# MCU.net
KiCad netlist of a schematic drawn in Altium Designer
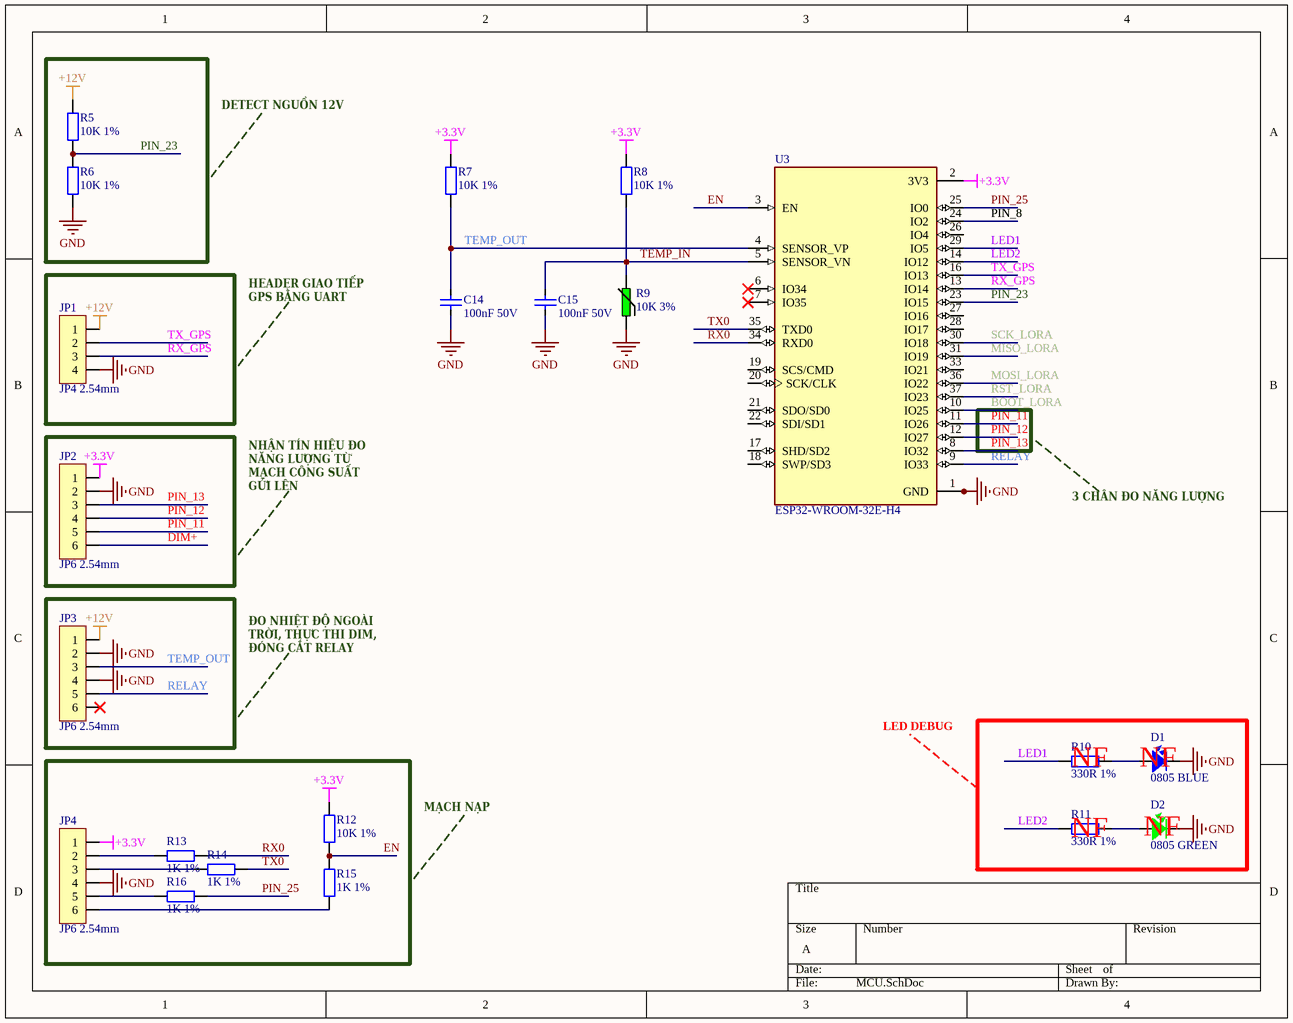
[diagram p0: MCU.SchDoc]

(export (version "E")
  (design (tool "Eeschema 10.0.6"))
  (components
    (comp (ref "C14")
      (value "100nF 50V")
      (footprint "CAP_SMD_0805")
      (description "0.1 µF ±10% 50V Ceramic Capacitor X7R 0805 (2012 Metric)")
      (fields
        (field (name "MANUFACTURER") "YAGEO")
        (field (name "MANUFACTURE PART NUMBER") "CC0805KRX7R9BB104")
      )
      (libsource (lib "Nhatkhongbuon") (part "C0805_MLCC_100nF_50V"))
    )
    (comp (ref "C15")
      (value "100nF 50V")
      (footprint "CAP_SMD_0805")
      (description "0.1 µF ±10% 50V Ceramic Capacitor X7R 0805 (2012 Metric)")
      (fields
        (field (name "MANUFACTURER") "YAGEO")
        (field (name "MANUFACTURE PART NUMBER") "CC0805KRX7R9BB104")
      )
      (libsource (lib "Nhatkhongbuon") (part "C0805_MLCC_100nF_50V"))
    )
    (comp (ref "D1")
      (value "0805 BLUE")
      (footprint "LED-0805-Blue")
      (description "Blue 470nm LED Indication - Discrete 3.2V 0805 (2012 Metric)")
      (fields
        (field (name "MANUFACTURER") "Würth Elektronik")
        (field (name "MANUFACTURE PART NUMBER") "150080BS75000")
      )
      (libsource (lib "Nhatkhongbuon") (part "LED_0805_BLUE"))
    )
    (comp (ref "D2")
      (value "0805 GREEN")
      (footprint "LED-0805-Green")
      (description "Green 520nm LED Indication - Discrete 3.2V 0805 (2012 Metric)")
      (fields
        (field (name "MANUFACTURER") "Würth Elektronik")
        (field (name "MANUFACTURE PART NUMBER") "150080GS75000")
      )
      (libsource (lib "Nhatkhongbuon") (part "LED_0805_GREEN"))
    )
    (comp (ref "JP1")
      (value "JP4 2.54mm")
      (footprint "JP4_M")
      (description "Connector Header Through Hole 4 position 0.100\" (2.54mm)")
      (fields
        (field (name "MANUFACTURER") "Würth Elektronik")
        (field (name "MANUFACTURE PART NUMBER") "61300411121")
      )
      (libsource (lib "Nhatkhongbuon") (part "JP4M"))
    )
    (comp (ref "JP2")
      (value "JP6 2.54mm")
      (footprint "JP6_M")
      (description "Connector Header Through Hole 6 position 0.100\" (2.54mm)")
      (fields
        (field (name "MANUFACTURER") "Würth Elektronik")
        (field (name "MANUFACTURE PART NUMBER") "61300611121")
      )
      (libsource (lib "Nhatkhongbuon") (part "JP6M"))
    )
    (comp (ref "JP3")
      (value "JP6 2.54mm")
      (footprint "JP6_M")
      (description "Connector Header Through Hole 6 position 0.100\" (2.54mm)")
      (fields
        (field (name "MANUFACTURER") "Würth Elektronik")
        (field (name "MANUFACTURE PART NUMBER") "61300611121")
      )
      (libsource (lib "Nhatkhongbuon") (part "JP6M"))
    )
    (comp (ref "JP4")
      (value "JP6 2.54mm")
      (footprint "JP6_M")
      (description "Connector Header Through Hole 6 position 0.100\" (2.54mm)")
      (fields
        (field (name "MANUFACTURER") "Würth Elektronik")
        (field (name "MANUFACTURE PART NUMBER") "61300611121")
      )
      (libsource (lib "Nhatkhongbuon") (part "JP6M"))
    )
    (comp (ref "R5")
      (value "10K 1%")
      (footprint "RES_SMD_0805")
      (description "10 kOhms ±1% 0.125W, 1/8W Chip Resistor 0805 (2012 Metric) Moisture Resistant Thick Film")
      (fields
        (field (name "MANUFACTURER") "YAGEO")
        (field (name "MANUFACTURE PART NUMBER") "RC0805FR-0710KL")
      )
      (libsource (lib "Nhatkhongbuon") (part "R0805_10K"))
    )
    (comp (ref "R6")
      (value "10K 1%")
      (footprint "RES_SMD_0805")
      (description "10 kOhms ±1% 0.125W, 1/8W Chip Resistor 0805 (2012 Metric) Moisture Resistant Thick Film")
      (fields
        (field (name "MANUFACTURER") "YAGEO")
        (field (name "MANUFACTURE PART NUMBER") "RC0805FR-0710KL")
      )
      (libsource (lib "Nhatkhongbuon") (part "R0805_10K"))
    )
    (comp (ref "R7")
      (value "10K 1%")
      (footprint "RES_SMD_0805")
      (description "10 kOhms ±1% 0.125W, 1/8W Chip Resistor 0805 (2012 Metric) Moisture Resistant Thick Film")
      (fields
        (field (name "MANUFACTURER") "YAGEO")
        (field (name "MANUFACTURE PART NUMBER") "RC0805FR-0710KL")
      )
      (libsource (lib "Nhatkhongbuon") (part "R0805_10K"))
    )
    (comp (ref "R8")
      (value "10K 1%")
      (footprint "RES_SMD_0805")
      (description "10 kOhms ±1% 0.125W, 1/8W Chip Resistor 0805 (2012 Metric) Moisture Resistant Thick Film")
      (fields
        (field (name "MANUFACTURER") "YAGEO")
        (field (name "MANUFACTURE PART NUMBER") "RC0805FR-0710KL")
      )
      (libsource (lib "Nhatkhongbuon") (part "R0805_10K"))
    )
    (comp (ref "R9")
      (value "10K 3%")
      (footprint "NTC_2.54.")
      (description "NTC Thermistor 10k Bead")
      (fields
        (field (name "MANUFACTURER") "Vishay Beyschlag/Draloric/BC Components")
        (field (name "MANUFACTURE PART NUMBER") "NTCLE203E3103HB0")
      )
      (libsource (lib "Nhatkhongbuon") (part "NTC_10K_"))
    )
    (comp (ref "R10")
      (value "330R 1%")
      (footprint "RES_SMD_0805")
      (description "330 Ohms ±1% 0.125W, 1/8W Chip Resistor 0805 (2012 Metric) Automotive AEC-Q200 Thick Film")
      (fields
        (field (name "MANUFACTURER") "Stackpole Electronics Inc")
        (field (name "MANUFACTURE PART NUMBER") "RMCF0805FT330R")
      )
      (libsource (lib "Nhatkhongbuon") (part "R0805_330R"))
    )
    (comp (ref "R11")
      (value "330R 1%")
      (footprint "RES_SMD_0805")
      (description "330 Ohms ±1% 0.125W, 1/8W Chip Resistor 0805 (2012 Metric) Automotive AEC-Q200 Thick Film")
      (fields
        (field (name "MANUFACTURER") "Stackpole Electronics Inc")
        (field (name "MANUFACTURE PART NUMBER") "RMCF0805FT330R")
      )
      (libsource (lib "Nhatkhongbuon") (part "R0805_330R"))
    )
    (comp (ref "R12")
      (value "10K 1%")
      (footprint "RES_SMD_0805")
      (description "10 kOhms ±1% 0.125W, 1/8W Chip Resistor 0805 (2012 Metric) Moisture Resistant Thick Film")
      (fields
        (field (name "MANUFACTURER") "YAGEO")
        (field (name "MANUFACTURE PART NUMBER") "RC0805FR-0710KL")
      )
      (libsource (lib "Nhatkhongbuon") (part "R0805_10K"))
    )
    (comp (ref "R13")
      (value "1K 1%")
      (footprint "RES_SMD_0805")
      (description "1 kOhms ±1% 0.125W, 1/8W Chip Resistor 0805 (2012 Metric) Moisture Resistant Thick Film")
      (fields
        (field (name "MANUFACTURER") "YAGEO")
        (field (name "MANUFACTURE PART NUMBER") "311-1.00KCRCT-ND")
      )
      (libsource (lib "Nhatkhongbuon") (part "R0805_1K"))
    )
    (comp (ref "R14")
      (value "1K 1%")
      (footprint "RES_SMD_0805")
      (description "1 kOhms ±1% 0.125W, 1/8W Chip Resistor 0805 (2012 Metric) Moisture Resistant Thick Film")
      (fields
        (field (name "MANUFACTURER") "YAGEO")
        (field (name "MANUFACTURE PART NUMBER") "311-1.00KCRCT-ND")
      )
      (libsource (lib "Nhatkhongbuon") (part "R0805_1K"))
    )
    (comp (ref "R15")
      (value "1K 1%")
      (footprint "RES_SMD_0805")
      (description "1 kOhms ±1% 0.125W, 1/8W Chip Resistor 0805 (2012 Metric) Moisture Resistant Thick Film")
      (fields
        (field (name "MANUFACTURER") "YAGEO")
        (field (name "MANUFACTURE PART NUMBER") "311-1.00KCRCT-ND")
      )
      (libsource (lib "Nhatkhongbuon") (part "R0805_1K"))
    )
    (comp (ref "R16")
      (value "1K 1%")
      (footprint "RES_SMD_0805")
      (description "1 kOhms ±1% 0.125W, 1/8W Chip Resistor 0805 (2012 Metric) Moisture Resistant Thick Film")
      (fields
        (field (name "MANUFACTURER") "YAGEO")
        (field (name "MANUFACTURE PART NUMBER") "311-1.00KCRCT-ND")
      )
      (libsource (lib "Nhatkhongbuon") (part "R0805_1K"))
    )
    (comp (ref "U3")
      (value "ESP32-WROOM-32E-H4")
      (footprint "ESP32-WROOM-32")
      (fields (field (name "MANUFACTURER") "Espressif Systems"))
      (libsource (lib "Nhatkhongbuon") (part "ESP32-WROOM-32E-H4"))
    )
  )
  (nets
    (net (code "1") (name "+3.3V") (class "Default")
      (node (ref "JP2") (pin "1") (pinfunction "1_1") (pintype "passive"))
      (node (ref "JP4") (pin "1") (pinfunction "1_1") (pintype "passive"))
      (node (ref "R12") (pin "2") (pinfunction "2_2") (pintype "passive"))
      (node (ref "R7") (pin "2") (pinfunction "2_2") (pintype "passive"))
      (node (ref "R8") (pin "2") (pinfunction "2_2") (pintype "passive"))
      (node (ref "U3") (pin "2") (pinfunction "3V3_2") (pintype "power_in"))
    )
    (net (code "2") (name "+12V") (class "Default")
      (node (ref "JP1") (pin "1") (pinfunction "1_1") (pintype "passive"))
      (node (ref "JP3") (pin "1") (pinfunction "1_1") (pintype "passive"))
      (node (ref "R5") (pin "2") (pinfunction "2_2") (pintype "passive"))
    )
    (net (code "3") (name "/BOOT_LORA") (class "Default")
      (node (ref "U3") (pin "10") (pinfunction "IO25_10") (pintype "bidirectional"))
    )
    (net (code "4") (name "/DIM+") (class "Default")
      (node (ref "JP2") (pin "6") (pinfunction "6_6") (pintype "passive"))
    )
    (net (code "5") (name "/EN") (class "Default")
      (node (ref "R12") (pin "1") (pinfunction "1_1") (pintype "passive"))
      (node (ref "R15") (pin "2") (pinfunction "2_2") (pintype "passive"))
      (node (ref "U3") (pin "3") (pinfunction "EN_3") (pintype "input"))
    )
    (net (code "6") (name "/LED1") (class "Default")
      (node (ref "R10") (pin "1") (pinfunction "1_1") (pintype "passive"))
      (node (ref "U3") (pin "29") (pinfunction "IO5_29") (pintype "bidirectional"))
    )
    (net (code "7") (name "/LED2") (class "Default")
      (node (ref "R11") (pin "1") (pinfunction "1_1") (pintype "passive"))
      (node (ref "U3") (pin "14") (pinfunction "IO12_14") (pintype "bidirectional"))
    )
    (net (code "8") (name "/MISO_LORA") (class "Default")
      (node (ref "U3") (pin "31") (pinfunction "IO19_31") (pintype "bidirectional"))
    )
    (net (code "9") (name "/MOSI_LORA") (class "Default")
      (node (ref "U3") (pin "36") (pinfunction "IO22_36") (pintype "bidirectional"))
    )
    (net (code "10") (name "/PIN_8") (class "Default")
      (node (ref "U3") (pin "24") (pinfunction "IO2_24") (pintype "bidirectional"))
    )
    (net (code "11") (name "/PIN_11") (class "Default")
      (node (ref "JP2") (pin "5") (pinfunction "5_5") (pintype "passive"))
      (node (ref "U3") (pin "11") (pinfunction "IO26_11") (pintype "bidirectional"))
    )
    (net (code "12") (name "/PIN_12") (class "Default")
      (node (ref "JP2") (pin "4") (pinfunction "4_4") (pintype "passive"))
      (node (ref "U3") (pin "12") (pinfunction "IO27_12") (pintype "bidirectional"))
    )
    (net (code "13") (name "/PIN_13") (class "Default")
      (node (ref "JP2") (pin "3") (pinfunction "3_3") (pintype "passive"))
      (node (ref "U3") (pin "8") (pinfunction "IO32_8") (pintype "bidirectional"))
    )
    (net (code "14") (name "/PIN_23") (class "Default")
      (node (ref "R5") (pin "1") (pinfunction "1_1") (pintype "passive"))
      (node (ref "R6") (pin "2") (pinfunction "2_2") (pintype "passive"))
      (node (ref "U3") (pin "23") (pinfunction "IO15_23") (pintype "bidirectional"))
    )
    (net (code "15") (name "/PIN_25") (class "Default")
      (node (ref "R16") (pin "2") (pinfunction "2_2") (pintype "passive"))
      (node (ref "U3") (pin "25") (pinfunction "IO0_25") (pintype "bidirectional"))
    )
    (net (code "16") (name "/RELAY") (class "Default")
      (node (ref "JP3") (pin "5") (pinfunction "5_5") (pintype "passive"))
      (node (ref "U3") (pin "9") (pinfunction "IO33_9") (pintype "bidirectional"))
    )
    (net (code "17") (name "/RST_LORA") (class "Default")
      (node (ref "U3") (pin "37") (pinfunction "IO23_37") (pintype "bidirectional"))
    )
    (net (code "18") (name "/RX0") (class "Default")
      (node (ref "R13") (pin "2") (pinfunction "2_2") (pintype "passive"))
      (node (ref "U3") (pin "34") (pinfunction "RXD0_34") (pintype "bidirectional"))
    )
    (net (code "19") (name "/RX_GPS") (class "Default")
      (node (ref "JP1") (pin "3") (pinfunction "3_3") (pintype "passive"))
      (node (ref "U3") (pin "13") (pinfunction "IO14_13") (pintype "bidirectional"))
    )
    (net (code "20") (name "/SCK_LORA") (class "Default")
      (node (ref "U3") (pin "30") (pinfunction "IO18_30") (pintype "bidirectional"))
    )
    (net (code "21") (name "/TEMP_IN") (class "Default")
      (node (ref "C15") (pin "2") (pinfunction "2_2") (pintype "passive"))
      (node (ref "R8") (pin "1") (pinfunction "1_1") (pintype "passive"))
      (node (ref "R9") (pin "2") (pinfunction "2_2") (pintype "passive"))
      (node (ref "U3") (pin "5") (pinfunction "SENSOR_VN_5") (pintype "input"))
    )
    (net (code "22") (name "/TEMP_OUT") (class "Default")
      (node (ref "C14") (pin "2") (pinfunction "2_2") (pintype "passive"))
      (node (ref "JP3") (pin "3") (pinfunction "3_3") (pintype "passive"))
      (node (ref "R7") (pin "1") (pinfunction "1_1") (pintype "passive"))
      (node (ref "U3") (pin "4") (pinfunction "SENSOR_VP_4") (pintype "input"))
    )
    (net (code "23") (name "/TX0") (class "Default")
      (node (ref "R14") (pin "2") (pinfunction "2_2") (pintype "passive"))
      (node (ref "U3") (pin "35") (pinfunction "TXD0_35") (pintype "bidirectional"))
    )
    (net (code "24") (name "/TX_GPS") (class "Default")
      (node (ref "JP1") (pin "2") (pinfunction "2_2") (pintype "passive"))
      (node (ref "U3") (pin "16") (pinfunction "IO13_16") (pintype "bidirectional"))
    )
    (net (code "25") (name "GND") (class "Default")
      (node (ref "C14") (pin "1") (pinfunction "1_1") (pintype "passive"))
      (node (ref "C15") (pin "1") (pinfunction "1_1") (pintype "passive"))
      (node (ref "D1") (pin "2") (pinfunction "2_2") (pintype "passive"))
      (node (ref "D2") (pin "2") (pinfunction "2_2") (pintype "passive"))
      (node (ref "JP1") (pin "4") (pinfunction "4_4") (pintype "passive"))
      (node (ref "JP2") (pin "2") (pinfunction "2_2") (pintype "passive"))
      (node (ref "JP3") (pin "2") (pinfunction "2_2") (pintype "passive"))
      (node (ref "JP3") (pin "4") (pinfunction "4_4") (pintype "passive"))
      (node (ref "JP4") (pin "4") (pinfunction "4_4") (pintype "passive"))
      (node (ref "R6") (pin "1") (pinfunction "1_1") (pintype "passive"))
      (node (ref "R9") (pin "1") (pinfunction "1_1") (pintype "passive"))
      (node (ref "U3") (pin "1") (pinfunction "GND_1") (pintype "power_in"))
      (node (ref "U3") (pin "15") (pinfunction "GND_15") (pintype "power_in"))
      (node (ref "U3") (pin "38") (pinfunction "GND_38") (pintype "power_in"))
      (node (ref "U3") (pin "39_1") (pinfunction "GND_39_1") (pintype "power_in"))
      (node (ref "U3") (pin "39_10") (pinfunction "GND_39_10") (pintype "power_in"))
      (node (ref "U3") (pin "39_11") (pinfunction "GND_39_11") (pintype "power_in"))
      (node (ref "U3") (pin "39_12") (pinfunction "GND_39_12") (pintype "power_in"))
      (node (ref "U3") (pin "39_13") (pinfunction "GND_39_13") (pintype "power_in"))
      (node (ref "U3") (pin "39_14") (pinfunction "GND_39_14") (pintype "power_in"))
      (node (ref "U3") (pin "39_15") (pinfunction "GND_39_15") (pintype "power_in"))
      (node (ref "U3") (pin "39_16") (pinfunction "GND_39_16") (pintype "power_in"))
      (node (ref "U3") (pin "39_17") (pinfunction "GND_39_17") (pintype "power_in"))
      (node (ref "U3") (pin "39_18") (pinfunction "GND_39_18") (pintype "power_in"))
      (node (ref "U3") (pin "39_19") (pinfunction "GND_39_19") (pintype "power_in"))
      (node (ref "U3") (pin "39_2") (pinfunction "GND_39_2") (pintype "power_in"))
      (node (ref "U3") (pin "39_20") (pinfunction "GND_39_20") (pintype "power_in"))
      (node (ref "U3") (pin "39_21") (pinfunction "GND_39_21") (pintype "power_in"))
      (node (ref "U3") (pin "39_3") (pinfunction "GND_39_3") (pintype "power_in"))
      (node (ref "U3") (pin "39_4") (pinfunction "GND_39_4") (pintype "power_in"))
      (node (ref "U3") (pin "39_5") (pinfunction "GND_39_5") (pintype "power_in"))
      (node (ref "U3") (pin "39_6") (pinfunction "GND_39_6") (pintype "power_in"))
      (node (ref "U3") (pin "39_7") (pinfunction "GND_39_7") (pintype "power_in"))
      (node (ref "U3") (pin "39_8") (pinfunction "GND_39_8") (pintype "power_in"))
      (node (ref "U3") (pin "39_9") (pinfunction "GND_39_9") (pintype "power_in"))
    )
    (net (code "26") (name "Net-(D1-Pad1)") (class "Default")
      (node (ref "D1") (pin "1") (pinfunction "1_1") (pintype "passive"))
      (node (ref "R10") (pin "2") (pinfunction "2_2") (pintype "passive"))
    )
    (net (code "27") (name "Net-(D2-Pad1)") (class "Default")
      (node (ref "D2") (pin "1") (pinfunction "1_1") (pintype "passive"))
      (node (ref "R11") (pin "2") (pinfunction "2_2") (pintype "passive"))
    )
    (net (code "28") (name "Net-(JP4-Pad2)") (class "Default")
      (node (ref "JP4") (pin "2") (pinfunction "2_2") (pintype "passive"))
      (node (ref "R13") (pin "1") (pinfunction "1_1") (pintype "passive"))
    )
    (net (code "29") (name "Net-(JP4-Pad3)") (class "Default")
      (node (ref "JP4") (pin "3") (pinfunction "3_3") (pintype "passive"))
      (node (ref "R14") (pin "1") (pinfunction "1_1") (pintype "passive"))
    )
    (net (code "30") (name "Net-(JP4-Pad5)") (class "Default")
      (node (ref "JP4") (pin "5") (pinfunction "5_5") (pintype "passive"))
      (node (ref "R16") (pin "1") (pinfunction "1_1") (pintype "passive"))
    )
    (net (code "31") (name "Net-(JP4-Pad6)") (class "Default")
      (node (ref "JP4") (pin "6") (pinfunction "6_6") (pintype "passive"))
      (node (ref "R15") (pin "1") (pinfunction "1_1") (pintype "passive"))
    )
    (net (code "32") (name "unconnected-(JP3-Pad6)") (class "Default")
      (node (ref "JP3") (pin "6") (pinfunction "6_6") (pintype "passive+no_connect"))
    )
    (net (code "33") (name "unconnected-(U3-IO4-Pad26)") (class "Default")
      (node (ref "U3") (pin "26") (pinfunction "IO4_26") (pintype "bidirectional"))
    )
    (net (code "34") (name "unconnected-(U3-IO16-Pad27)") (class "Default")
      (node (ref "U3") (pin "27") (pinfunction "IO16_27") (pintype "bidirectional"))
    )
    (net (code "35") (name "unconnected-(U3-IO17-Pad28)") (class "Default")
      (node (ref "U3") (pin "28") (pinfunction "IO17_28") (pintype "bidirectional"))
    )
    (net (code "36") (name "unconnected-(U3-IO21-Pad33)") (class "Default")
      (node (ref "U3") (pin "33") (pinfunction "IO21_33") (pintype "bidirectional"))
    )
    (net (code "37") (name "unconnected-(U3-IO34-Pad6)") (class "Default")
      (node (ref "U3") (pin "6") (pinfunction "IO34_6") (pintype "input+no_connect"))
    )
    (net (code "38") (name "unconnected-(U3-IO35-Pad7)") (class "Default")
      (node (ref "U3") (pin "7") (pinfunction "IO35_7") (pintype "input+no_connect"))
    )
    (net (code "39") (name "unconnected-(U3-SCK{slash}CLK-Pad20)") (class "Default")
      (node (ref "U3") (pin "20") (pinfunction "SCK/CLK_20") (pintype "bidirectional"))
    )
    (net (code "40") (name "unconnected-(U3-SCS{slash}CMD-Pad19)") (class "Default")
      (node (ref "U3") (pin "19") (pinfunction "SCS/CMD_19") (pintype "bidirectional"))
    )
    (net (code "41") (name "unconnected-(U3-SDI{slash}SD1-Pad22)") (class "Default")
      (node (ref "U3") (pin "22") (pinfunction "SDI/SD1_22") (pintype "bidirectional"))
    )
    (net (code "42") (name "unconnected-(U3-SDO{slash}SD0-Pad21)") (class "Default")
      (node (ref "U3") (pin "21") (pinfunction "SDO/SD0_21") (pintype "bidirectional"))
    )
    (net (code "43") (name "unconnected-(U3-SHD{slash}SD2-Pad17)") (class "Default")
      (node (ref "U3") (pin "17") (pinfunction "SHD/SD2_17") (pintype "bidirectional"))
    )
    (net (code "44") (name "unconnected-(U3-SWP{slash}SD3-Pad18)") (class "Default")
      (node (ref "U3") (pin "18") (pinfunction "SWP/SD3_18") (pintype "bidirectional"))
    )
  )
)
